# sdram_xsds.net
KiCad netlist of a schematic drawn in Altium Designer
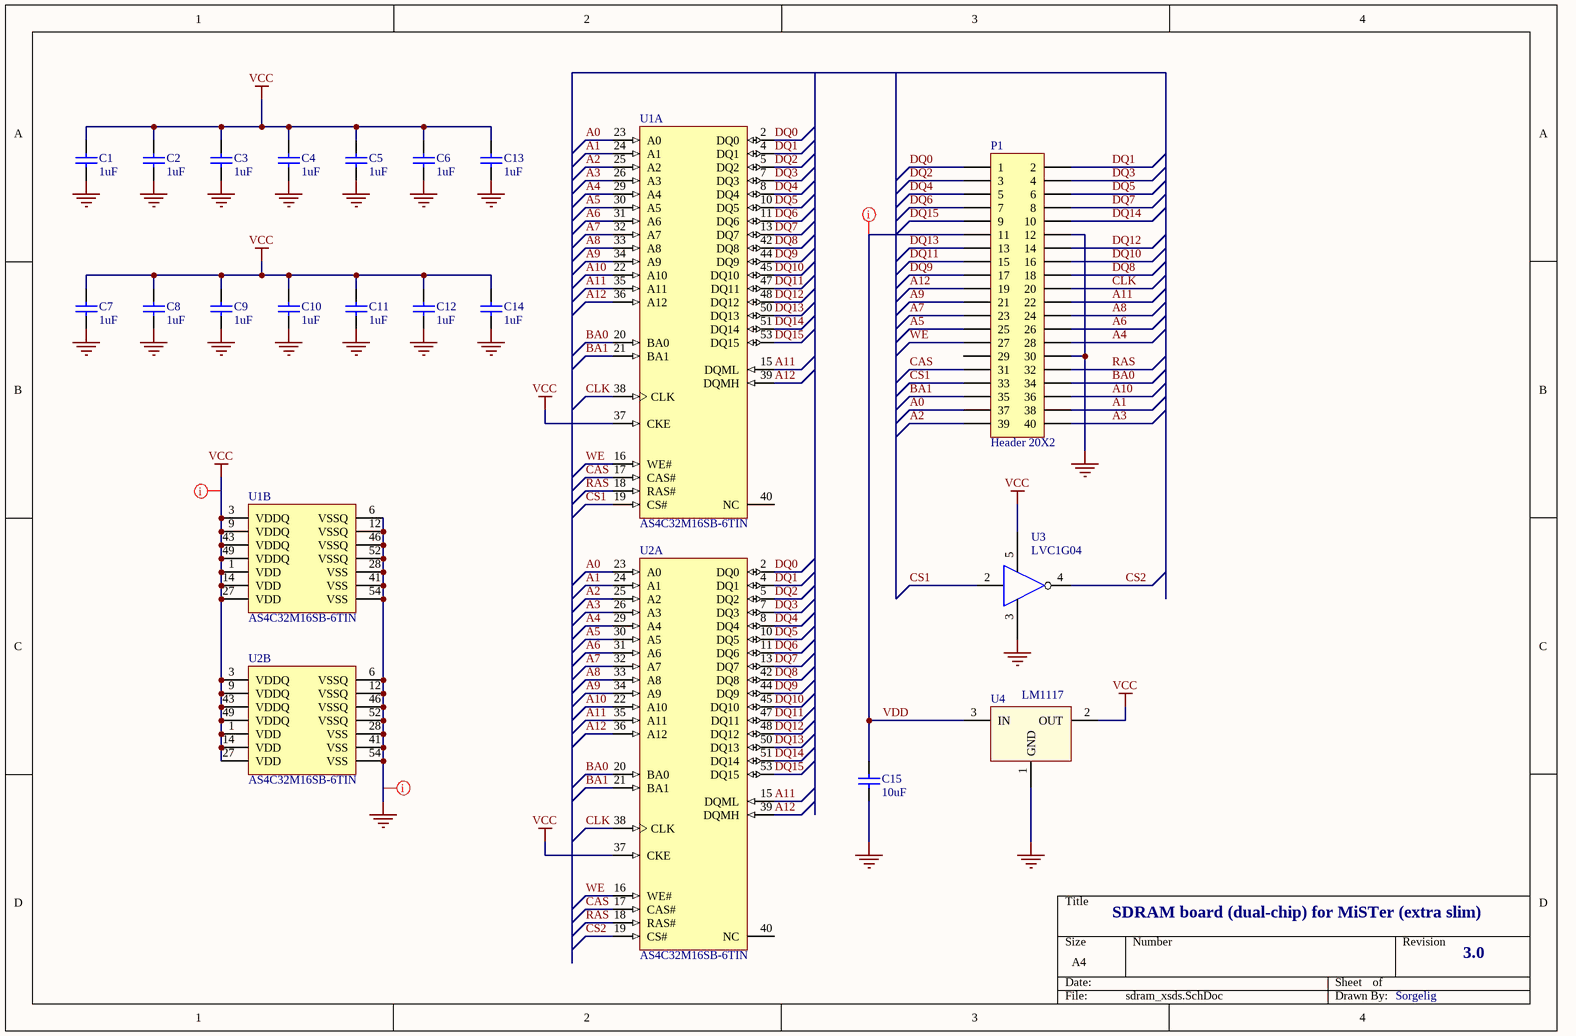
[diagram p0: sdram_xsds.SchDoc]

(export (version "E")
  (design (tool "Eeschema 10.0.6"))
  (components
    (comp (ref "C1")
      (value "1uF")
      (footprint "C0805")
      (description "Ceramic Chip Capacitor - Standard")
      (fields (field (name "Comment") "C0805") (field (name "PUBLISHER") "Altium Limited"))
      (libsource (lib "lib") (part "C0805"))
    )
    (comp (ref "C2")
      (value "1uF")
      (footprint "C0805")
      (description "Ceramic Chip Capacitor - Standard")
      (fields (field (name "Comment") "C0805") (field (name "PUBLISHER") "Altium Limited"))
      (libsource (lib "lib") (part "C0805"))
    )
    (comp (ref "C3")
      (value "1uF")
      (footprint "C0805")
      (description "Ceramic Chip Capacitor - Standard")
      (fields (field (name "Comment") "C0805") (field (name "PUBLISHER") "Altium Limited"))
      (libsource (lib "lib") (part "C0805"))
    )
    (comp (ref "C4")
      (value "1uF")
      (footprint "C0805")
      (description "Ceramic Chip Capacitor - Standard")
      (fields (field (name "Comment") "C0805") (field (name "PUBLISHER") "Altium Limited"))
      (libsource (lib "lib") (part "C0805"))
    )
    (comp (ref "C5")
      (value "1uF")
      (footprint "C0805")
      (description "Ceramic Chip Capacitor - Standard")
      (fields (field (name "Comment") "+") (field (name "PUBLISHER") "Altium Limited"))
      (libsource (lib "lib") (part "C0805"))
    )
    (comp (ref "C6")
      (value "1uF")
      (footprint "C0805")
      (description "Ceramic Chip Capacitor - Standard")
      (fields (field (name "Comment") "+") (field (name "PUBLISHER") "Altium Limited"))
      (libsource (lib "lib") (part "C0805"))
    )
    (comp (ref "C7")
      (value "1uF")
      (footprint "C0805")
      (description "Ceramic Chip Capacitor - Standard")
      (fields (field (name "Comment") "C0805") (field (name "PUBLISHER") "Altium Limited"))
      (libsource (lib "lib") (part "C0805"))
    )
    (comp (ref "C8")
      (value "1uF")
      (footprint "C0805")
      (description "Ceramic Chip Capacitor - Standard")
      (fields (field (name "Comment") "C0805") (field (name "PUBLISHER") "Altium Limited"))
      (libsource (lib "lib") (part "C0805"))
    )
    (comp (ref "C9")
      (value "1uF")
      (footprint "C0805")
      (description "Ceramic Chip Capacitor - Standard")
      (fields (field (name "Comment") "+") (field (name "PUBLISHER") "Altium Limited"))
      (libsource (lib "lib") (part "C0805"))
    )
    (comp (ref "C10")
      (value "1uF")
      (footprint "C0805")
      (description "Ceramic Chip Capacitor - Standard")
      (fields (field (name "Comment") "C0805") (field (name "PUBLISHER") "Altium Limited"))
      (libsource (lib "lib") (part "C0805"))
    )
    (comp (ref "C11")
      (value "1uF")
      (footprint "C0805")
      (description "Ceramic Chip Capacitor - Standard")
      (fields (field (name "Comment") "C0805") (field (name "PUBLISHER") "Altium Limited"))
      (libsource (lib "lib") (part "C0805"))
    )
    (comp (ref "C12")
      (value "1uF")
      (footprint "C0805")
      (description "Ceramic Chip Capacitor - Standard")
      (fields (field (name "Comment") "+") (field (name "PUBLISHER") "Altium Limited"))
      (libsource (lib "lib") (part "C0805"))
    )
    (comp (ref "C13")
      (value "1uF")
      (footprint "C0805")
      (description "Ceramic Chip Capacitor - Standard")
      (fields (field (name "Comment") "+") (field (name "PUBLISHER") "Altium Limited"))
      (libsource (lib "lib") (part "C0805"))
    )
    (comp (ref "C14")
      (value "1uF")
      (footprint "C0805")
      (description "Ceramic Chip Capacitor - Standard")
      (fields (field (name "Comment") "+") (field (name "PUBLISHER") "Altium Limited"))
      (libsource (lib "lib") (part "C0805"))
    )
    (comp (ref "C15")
      (value "10uF")
      (footprint "C0805")
      (description "Ceramic Chip Capacitor - Standard")
      (fields (field (name "Comment") "+") (field (name "PUBLISHER") "Altium Limited"))
      (libsource (lib "lib") (part "C0805"))
    )
    (comp (ref "P1")
      (value "Header 20X2")
      (footprint "HDR20x2_90 SMD")
      (description "Header, 20-Pin, Dual row")
      (fields (field (name "PUBLISHER") "Altium Limited"))
      (libsource (lib "Miscellaneous Connectors") (part "Header 20X2"))
    )
    (comp (ref "U1")
      (value "AS4C32M16SB-6TIN")
      (footprint "TSOP54")
      (description "256Mb SDR SDRAM, 16Mb x 16, 6ns, 3.3V, 54-Pin TSOP")
      (fields (field (name "VOLTAGE") "3.3V") (field (name "MANUFACTURER") "Micron"))
      (libsource (lib "lib") (part "AS4C16M16SA-6TCN"))
    )
    (comp (ref "U2")
      (value "AS4C32M16SB-6TIN")
      (footprint "TSOP54")
      (description "256Mb SDR SDRAM, 16Mb x 16, 6ns, 3.3V, 54-Pin TSOP")
      (fields (field (name "VOLTAGE") "3.3V") (field (name "MANUFACTURER") "Micron"))
      (libsource (lib "lib") (part "AS4C16M16SA-6TCN"))
    )
    (comp (ref "U3")
      (value "LVC1G04")
      (footprint "SOT23/70-5")
      (description "INVERTER")
      (libsource (lib "lib") (part "LVC1G04"))
    )
    (comp (ref "U4") (value "LM1117") (footprint "SOT89") (libsource (lib "lib") (part "LM1117")))
  )
  (nets
    (net (code "1") (name "/A0") (class "Default")
      (node (ref "P1") (pin "37") (pinfunction "37_37") (pintype "passive"))
      (node (ref "U1") (pin "23") (pinfunction "A0_23") (pintype "input"))
      (node (ref "U2") (pin "23") (pinfunction "A0_23") (pintype "input"))
    )
    (net (code "2") (name "/A1") (class "Default")
      (node (ref "P1") (pin "38") (pinfunction "38_38") (pintype "passive"))
      (node (ref "U1") (pin "24") (pinfunction "A1_24") (pintype "input"))
      (node (ref "U2") (pin "24") (pinfunction "A1_24") (pintype "input"))
    )
    (net (code "3") (name "/A2") (class "Default")
      (node (ref "P1") (pin "39") (pinfunction "39_39") (pintype "passive"))
      (node (ref "U1") (pin "25") (pinfunction "A2_25") (pintype "input"))
      (node (ref "U2") (pin "25") (pinfunction "A2_25") (pintype "input"))
    )
    (net (code "4") (name "/A3") (class "Default")
      (node (ref "P1") (pin "40") (pinfunction "40_40") (pintype "passive"))
      (node (ref "U1") (pin "26") (pinfunction "A3_26") (pintype "input"))
      (node (ref "U2") (pin "26") (pinfunction "A3_26") (pintype "input"))
    )
    (net (code "5") (name "/A4") (class "Default")
      (node (ref "P1") (pin "28") (pinfunction "28_28") (pintype "passive"))
      (node (ref "U1") (pin "29") (pinfunction "A4_29") (pintype "input"))
      (node (ref "U2") (pin "29") (pinfunction "A4_29") (pintype "input"))
    )
    (net (code "6") (name "/A5") (class "Default")
      (node (ref "P1") (pin "25") (pinfunction "25_25") (pintype "passive"))
      (node (ref "U1") (pin "30") (pinfunction "A5_30") (pintype "input"))
      (node (ref "U2") (pin "30") (pinfunction "A5_30") (pintype "input"))
    )
    (net (code "7") (name "/A6") (class "Default")
      (node (ref "P1") (pin "26") (pinfunction "26_26") (pintype "passive"))
      (node (ref "U1") (pin "31") (pinfunction "A6_31") (pintype "input"))
      (node (ref "U2") (pin "31") (pinfunction "A6_31") (pintype "input"))
    )
    (net (code "8") (name "/A7") (class "Default")
      (node (ref "P1") (pin "23") (pinfunction "23_23") (pintype "passive"))
      (node (ref "U1") (pin "32") (pinfunction "A7_32") (pintype "input"))
      (node (ref "U2") (pin "32") (pinfunction "A7_32") (pintype "input"))
    )
    (net (code "9") (name "/A8") (class "Default")
      (node (ref "P1") (pin "24") (pinfunction "24_24") (pintype "passive"))
      (node (ref "U1") (pin "33") (pinfunction "A8_33") (pintype "input"))
      (node (ref "U2") (pin "33") (pinfunction "A8_33") (pintype "input"))
    )
    (net (code "10") (name "/A9") (class "Default")
      (node (ref "P1") (pin "21") (pinfunction "21_21") (pintype "passive"))
      (node (ref "U1") (pin "34") (pinfunction "A9_34") (pintype "input"))
      (node (ref "U2") (pin "34") (pinfunction "A9_34") (pintype "input"))
    )
    (net (code "11") (name "/A10") (class "Default")
      (node (ref "P1") (pin "36") (pinfunction "36_36") (pintype "passive"))
      (node (ref "U1") (pin "22") (pinfunction "A10_22") (pintype "input"))
      (node (ref "U2") (pin "22") (pinfunction "A10_22") (pintype "input"))
    )
    (net (code "12") (name "/A11") (class "Default")
      (node (ref "P1") (pin "22") (pinfunction "22_22") (pintype "passive"))
      (node (ref "U1") (pin "15") (pinfunction "DQML_15") (pintype "input"))
      (node (ref "U1") (pin "35") (pinfunction "A11_35") (pintype "input"))
      (node (ref "U2") (pin "15") (pinfunction "DQML_15") (pintype "input"))
      (node (ref "U2") (pin "35") (pinfunction "A11_35") (pintype "input"))
    )
    (net (code "13") (name "/A12") (class "Default")
      (node (ref "P1") (pin "19") (pinfunction "19_19") (pintype "passive"))
      (node (ref "U1") (pin "36") (pinfunction "A12_36") (pintype "input"))
      (node (ref "U1") (pin "39") (pinfunction "DQMH_39") (pintype "input"))
      (node (ref "U2") (pin "36") (pinfunction "A12_36") (pintype "input"))
      (node (ref "U2") (pin "39") (pinfunction "DQMH_39") (pintype "input"))
    )
    (net (code "14") (name "/BA0") (class "Default")
      (node (ref "P1") (pin "34") (pinfunction "34_34") (pintype "passive"))
      (node (ref "U1") (pin "20") (pinfunction "BA0_20") (pintype "input"))
      (node (ref "U2") (pin "20") (pinfunction "BA0_20") (pintype "input"))
    )
    (net (code "15") (name "/BA1") (class "Default")
      (node (ref "P1") (pin "35") (pinfunction "35_35") (pintype "passive"))
      (node (ref "U1") (pin "21") (pinfunction "BA1_21") (pintype "input"))
      (node (ref "U2") (pin "21") (pinfunction "BA1_21") (pintype "input"))
    )
    (net (code "16") (name "/CAS") (class "Default")
      (node (ref "P1") (pin "31") (pinfunction "31_31") (pintype "passive"))
      (node (ref "U1") (pin "17") (pinfunction "CAS#_17") (pintype "input"))
      (node (ref "U2") (pin "17") (pinfunction "CAS#_17") (pintype "input"))
    )
    (net (code "17") (name "/CLK") (class "Default")
      (node (ref "P1") (pin "20") (pinfunction "20_20") (pintype "passive"))
      (node (ref "U1") (pin "38") (pinfunction "CLK_38") (pintype "input"))
      (node (ref "U2") (pin "38") (pinfunction "CLK_38") (pintype "input"))
    )
    (net (code "18") (name "/CS1") (class "Default")
      (node (ref "P1") (pin "33") (pinfunction "33_33") (pintype "passive"))
      (node (ref "U1") (pin "19") (pinfunction "CS#_19") (pintype "input"))
      (node (ref "U3") (pin "2") (pinfunction "A_2") (pintype "passive"))
    )
    (net (code "19") (name "/CS2") (class "Default")
      (node (ref "U2") (pin "19") (pinfunction "CS#_19") (pintype "input"))
      (node (ref "U3") (pin "4") (pinfunction "Y_4") (pintype "passive"))
    )
    (net (code "20") (name "/DQ0") (class "Default")
      (node (ref "P1") (pin "1") (pinfunction "1_1") (pintype "passive"))
      (node (ref "U1") (pin "2") (pinfunction "DQ0_2") (pintype "bidirectional"))
      (node (ref "U2") (pin "2") (pinfunction "DQ0_2") (pintype "bidirectional"))
    )
    (net (code "21") (name "/DQ1") (class "Default")
      (node (ref "P1") (pin "2") (pinfunction "2_2") (pintype "passive"))
      (node (ref "U1") (pin "4") (pinfunction "DQ1_4") (pintype "bidirectional"))
      (node (ref "U2") (pin "4") (pinfunction "DQ1_4") (pintype "bidirectional"))
    )
    (net (code "22") (name "/DQ2") (class "Default")
      (node (ref "P1") (pin "3") (pinfunction "3_3") (pintype "passive"))
      (node (ref "U1") (pin "5") (pinfunction "DQ2_5") (pintype "bidirectional"))
      (node (ref "U2") (pin "5") (pinfunction "DQ2_5") (pintype "bidirectional"))
    )
    (net (code "23") (name "/DQ3") (class "Default")
      (node (ref "P1") (pin "4") (pinfunction "4_4") (pintype "passive"))
      (node (ref "U1") (pin "7") (pinfunction "DQ3_7") (pintype "bidirectional"))
      (node (ref "U2") (pin "7") (pinfunction "DQ3_7") (pintype "bidirectional"))
    )
    (net (code "24") (name "/DQ4") (class "Default")
      (node (ref "P1") (pin "5") (pinfunction "5_5") (pintype "passive"))
      (node (ref "U1") (pin "8") (pinfunction "DQ4_8") (pintype "bidirectional"))
      (node (ref "U2") (pin "8") (pinfunction "DQ4_8") (pintype "bidirectional"))
    )
    (net (code "25") (name "/DQ5") (class "Default")
      (node (ref "P1") (pin "6") (pinfunction "6_6") (pintype "passive"))
      (node (ref "U1") (pin "10") (pinfunction "DQ5_10") (pintype "bidirectional"))
      (node (ref "U2") (pin "10") (pinfunction "DQ5_10") (pintype "bidirectional"))
    )
    (net (code "26") (name "/DQ6") (class "Default")
      (node (ref "P1") (pin "7") (pinfunction "7_7") (pintype "passive"))
      (node (ref "U1") (pin "11") (pinfunction "DQ6_11") (pintype "bidirectional"))
      (node (ref "U2") (pin "11") (pinfunction "DQ6_11") (pintype "bidirectional"))
    )
    (net (code "27") (name "/DQ7") (class "Default")
      (node (ref "P1") (pin "8") (pinfunction "8_8") (pintype "passive"))
      (node (ref "U1") (pin "13") (pinfunction "DQ7_13") (pintype "bidirectional"))
      (node (ref "U2") (pin "13") (pinfunction "DQ7_13") (pintype "bidirectional"))
    )
    (net (code "28") (name "/DQ8") (class "Default")
      (node (ref "P1") (pin "18") (pinfunction "18_18") (pintype "passive"))
      (node (ref "U1") (pin "42") (pinfunction "DQ8_42") (pintype "bidirectional"))
      (node (ref "U2") (pin "42") (pinfunction "DQ8_42") (pintype "bidirectional"))
    )
    (net (code "29") (name "/DQ9") (class "Default")
      (node (ref "P1") (pin "17") (pinfunction "17_17") (pintype "passive"))
      (node (ref "U1") (pin "44") (pinfunction "DQ9_44") (pintype "bidirectional"))
      (node (ref "U2") (pin "44") (pinfunction "DQ9_44") (pintype "bidirectional"))
    )
    (net (code "30") (name "/DQ10") (class "Default")
      (node (ref "P1") (pin "16") (pinfunction "16_16") (pintype "passive"))
      (node (ref "U1") (pin "45") (pinfunction "DQ10_45") (pintype "bidirectional"))
      (node (ref "U2") (pin "45") (pinfunction "DQ10_45") (pintype "bidirectional"))
    )
    (net (code "31") (name "/DQ11") (class "Default")
      (node (ref "P1") (pin "15") (pinfunction "15_15") (pintype "passive"))
      (node (ref "U1") (pin "47") (pinfunction "DQ11_47") (pintype "bidirectional"))
      (node (ref "U2") (pin "47") (pinfunction "DQ11_47") (pintype "bidirectional"))
    )
    (net (code "32") (name "/DQ12") (class "Default")
      (node (ref "P1") (pin "14") (pinfunction "14_14") (pintype "passive"))
      (node (ref "U1") (pin "48") (pinfunction "DQ12_48") (pintype "bidirectional"))
      (node (ref "U2") (pin "48") (pinfunction "DQ12_48") (pintype "bidirectional"))
    )
    (net (code "33") (name "/DQ13") (class "Default")
      (node (ref "P1") (pin "13") (pinfunction "13_13") (pintype "passive"))
      (node (ref "U1") (pin "50") (pinfunction "DQ13_50") (pintype "bidirectional"))
      (node (ref "U2") (pin "50") (pinfunction "DQ13_50") (pintype "bidirectional"))
    )
    (net (code "34") (name "/DQ14") (class "Default")
      (node (ref "P1") (pin "10") (pinfunction "10_10") (pintype "passive"))
      (node (ref "U1") (pin "51") (pinfunction "DQ14_51") (pintype "bidirectional"))
      (node (ref "U2") (pin "51") (pinfunction "DQ14_51") (pintype "bidirectional"))
    )
    (net (code "35") (name "/DQ15") (class "Default")
      (node (ref "P1") (pin "9") (pinfunction "9_9") (pintype "passive"))
      (node (ref "U1") (pin "53") (pinfunction "DQ15_53") (pintype "bidirectional"))
      (node (ref "U2") (pin "53") (pinfunction "DQ15_53") (pintype "bidirectional"))
    )
    (net (code "36") (name "/RAS") (class "Default")
      (node (ref "P1") (pin "32") (pinfunction "32_32") (pintype "passive"))
      (node (ref "U1") (pin "18") (pinfunction "RAS#_18") (pintype "input"))
      (node (ref "U2") (pin "18") (pinfunction "RAS#_18") (pintype "input"))
    )
    (net (code "37") (name "/VDD") (class "Default")
      (node (ref "C15") (pin "2") (pinfunction "2_2") (pintype "passive"))
      (node (ref "P1") (pin "11") (pinfunction "11_11") (pintype "power_in"))
      (node (ref "U4") (pin "3") (pinfunction "IN_3") (pintype "passive"))
    )
    (net (code "38") (name "/WE") (class "Default")
      (node (ref "P1") (pin "27") (pinfunction "27_27") (pintype "passive"))
      (node (ref "U1") (pin "16") (pinfunction "WE#_16") (pintype "input"))
      (node (ref "U2") (pin "16") (pinfunction "WE#_16") (pintype "input"))
    )
    (net (code "39") (name "GND") (class "Default")
      (node (ref "C1") (pin "1") (pinfunction "1_1") (pintype "passive"))
      (node (ref "C10") (pin "1") (pinfunction "1_1") (pintype "passive"))
      (node (ref "C11") (pin "1") (pinfunction "1_1") (pintype "passive"))
      (node (ref "C12") (pin "1") (pinfunction "1_1") (pintype "passive"))
      (node (ref "C13") (pin "1") (pinfunction "1_1") (pintype "passive"))
      (node (ref "C14") (pin "1") (pinfunction "1_1") (pintype "passive"))
      (node (ref "C15") (pin "1") (pinfunction "1_1") (pintype "passive"))
      (node (ref "C2") (pin "1") (pinfunction "1_1") (pintype "passive"))
      (node (ref "C3") (pin "1") (pinfunction "1_1") (pintype "passive"))
      (node (ref "C4") (pin "1") (pinfunction "1_1") (pintype "passive"))
      (node (ref "C5") (pin "1") (pinfunction "1_1") (pintype "passive"))
      (node (ref "C6") (pin "1") (pinfunction "1_1") (pintype "passive"))
      (node (ref "C7") (pin "1") (pinfunction "1_1") (pintype "passive"))
      (node (ref "C8") (pin "1") (pinfunction "1_1") (pintype "passive"))
      (node (ref "C9") (pin "1") (pinfunction "1_1") (pintype "passive"))
      (node (ref "P1") (pin "12") (pinfunction "12_12") (pintype "power_in"))
      (node (ref "P1") (pin "30") (pinfunction "30_30") (pintype "power_in"))
      (node (ref "U1") (pin "12") (pinfunction "VSSQ_12") (pintype "power_in"))
      (node (ref "U1") (pin "28") (pinfunction "VSS_28") (pintype "power_in"))
      (node (ref "U1") (pin "41") (pinfunction "VSS_41") (pintype "power_in"))
      (node (ref "U1") (pin "46") (pinfunction "VSSQ_46") (pintype "power_in"))
      (node (ref "U1") (pin "52") (pinfunction "VSSQ_52") (pintype "power_in"))
      (node (ref "U1") (pin "54") (pinfunction "VSS_54") (pintype "power_in"))
      (node (ref "U1") (pin "6") (pinfunction "VSSQ_6") (pintype "power_in"))
      (node (ref "U2") (pin "12") (pinfunction "VSSQ_12") (pintype "power_in"))
      (node (ref "U2") (pin "28") (pinfunction "VSS_28") (pintype "power_in"))
      (node (ref "U2") (pin "41") (pinfunction "VSS_41") (pintype "power_in"))
      (node (ref "U2") (pin "46") (pinfunction "VSSQ_46") (pintype "power_in"))
      (node (ref "U2") (pin "52") (pinfunction "VSSQ_52") (pintype "power_in"))
      (node (ref "U2") (pin "54") (pinfunction "VSS_54") (pintype "power_in"))
      (node (ref "U2") (pin "6") (pinfunction "VSSQ_6") (pintype "power_in"))
      (node (ref "U3") (pin "3") (pinfunction "GND_3") (pintype "passive"))
      (node (ref "U4") (pin "1") (pinfunction "GND_1") (pintype "passive"))
    )
    (net (code "40") (name "VCC") (class "Default")
      (node (ref "C1") (pin "2") (pinfunction "2_2") (pintype "passive"))
      (node (ref "C10") (pin "2") (pinfunction "2_2") (pintype "passive"))
      (node (ref "C11") (pin "2") (pinfunction "2_2") (pintype "passive"))
      (node (ref "C12") (pin "2") (pinfunction "2_2") (pintype "passive"))
      (node (ref "C13") (pin "2") (pinfunction "2_2") (pintype "passive"))
      (node (ref "C14") (pin "2") (pinfunction "2_2") (pintype "passive"))
      (node (ref "C2") (pin "2") (pinfunction "2_2") (pintype "passive"))
      (node (ref "C3") (pin "2") (pinfunction "2_2") (pintype "passive"))
      (node (ref "C4") (pin "2") (pinfunction "2_2") (pintype "passive"))
      (node (ref "C5") (pin "2") (pinfunction "2_2") (pintype "passive"))
      (node (ref "C6") (pin "2") (pinfunction "2_2") (pintype "passive"))
      (node (ref "C7") (pin "2") (pinfunction "2_2") (pintype "passive"))
      (node (ref "C8") (pin "2") (pinfunction "2_2") (pintype "passive"))
      (node (ref "C9") (pin "2") (pinfunction "2_2") (pintype "passive"))
      (node (ref "U1") (pin "1") (pinfunction "VDD_1") (pintype "power_in"))
      (node (ref "U1") (pin "14") (pinfunction "VDD_14") (pintype "power_in"))
      (node (ref "U1") (pin "27") (pinfunction "VDD_27") (pintype "power_in"))
      (node (ref "U1") (pin "3") (pinfunction "VDDQ_3") (pintype "power_in"))
      (node (ref "U1") (pin "37") (pinfunction "CKE_37") (pintype "input"))
      (node (ref "U1") (pin "43") (pinfunction "VDDQ_43") (pintype "power_in"))
      (node (ref "U1") (pin "49") (pinfunction "VDDQ_49") (pintype "power_in"))
      (node (ref "U1") (pin "9") (pinfunction "VDDQ_9") (pintype "power_in"))
      (node (ref "U2") (pin "1") (pinfunction "VDD_1") (pintype "power_in"))
      (node (ref "U2") (pin "14") (pinfunction "VDD_14") (pintype "power_in"))
      (node (ref "U2") (pin "27") (pinfunction "VDD_27") (pintype "power_in"))
      (node (ref "U2") (pin "3") (pinfunction "VDDQ_3") (pintype "power_in"))
      (node (ref "U2") (pin "37") (pinfunction "CKE_37") (pintype "input"))
      (node (ref "U2") (pin "43") (pinfunction "VDDQ_43") (pintype "power_in"))
      (node (ref "U2") (pin "49") (pinfunction "VDDQ_49") (pintype "power_in"))
      (node (ref "U2") (pin "9") (pinfunction "VDDQ_9") (pintype "power_in"))
      (node (ref "U3") (pin "5") (pinfunction "VCC_5") (pintype "passive"))
      (node (ref "U4") (pin "2") (pinfunction "OUT_2") (pintype "passive"))
    )
    (net (code "41") (name "unconnected-(P1-Pad29)") (class "Default")
      (node (ref "P1") (pin "29") (pinfunction "29_29") (pintype "power_in"))
    )
    (net (code "42") (name "unconnected-(U1A-NC-Pad40)") (class "Default")
      (node (ref "U1") (pin "40") (pinfunction "NC_40") (pintype "passive"))
    )
    (net (code "43") (name "unconnected-(U2A-NC-Pad40)") (class "Default")
      (node (ref "U2") (pin "40") (pinfunction "NC_40") (pintype "passive"))
    )
  )
)
